# Sheet1.net
KiCad netlist of a schematic drawn in Altium Designer
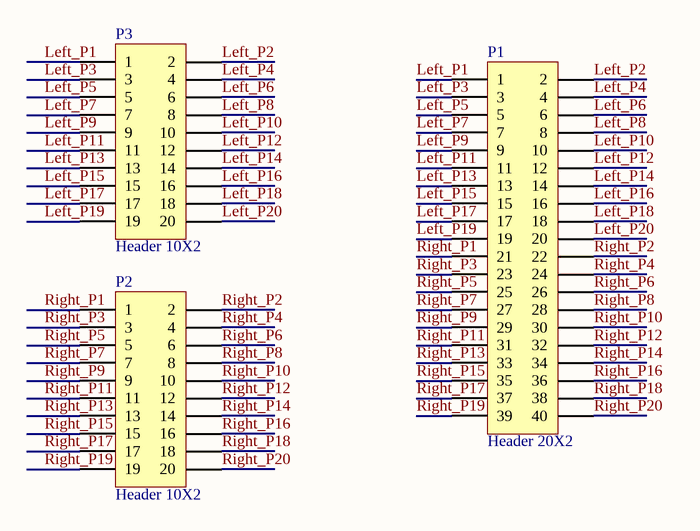
[diagram p0: Sheet1.SchDoc]

(export (version "E")
  (design (tool "Eeschema 10.0.6"))
  (components
    (comp (ref "P1")
      (value "Header 20X2")
      (footprint "BTB0.8con40Pin")
      (description "Header, 20-Pin, Dual row")
      (fields (field (name "PUBLISHER") "Altium Limited"))
      (libsource (lib "Miscellaneous Connectors") (part "Header 20X2"))
    )
    (comp (ref "P2")
      (value "Header 10X2")
      (footprint "HDR2X10")
      (description "Header, 10-Pin, Dual row")
      (fields (field (name "PUBLISHER") "Altium Limited"))
      (libsource (lib "Miscellaneous Connectors") (part "Header 10X2"))
    )
    (comp (ref "P3")
      (value "Header 10X2")
      (footprint "HDR2X10")
      (description "Header, 10-Pin, Dual row")
      (fields (field (name "PUBLISHER") "Altium Limited"))
      (libsource (lib "Miscellaneous Connectors") (part "Header 10X2"))
    )
  )
  (nets
    (net (code "1") (name "/Left_P1") (class "Default")
      (node (ref "P1") (pin "1") (pinfunction "1_1") (pintype "passive"))
      (node (ref "P3") (pin "1") (pinfunction "1_1") (pintype "passive"))
    )
    (net (code "2") (name "/Left_P2") (class "Default")
      (node (ref "P1") (pin "2") (pinfunction "2_2") (pintype "passive"))
      (node (ref "P3") (pin "2") (pinfunction "2_2") (pintype "passive"))
    )
    (net (code "3") (name "/Left_P3") (class "Default")
      (node (ref "P1") (pin "3") (pinfunction "3_3") (pintype "passive"))
      (node (ref "P3") (pin "3") (pinfunction "3_3") (pintype "passive"))
    )
    (net (code "4") (name "/Left_P4") (class "Default")
      (node (ref "P1") (pin "4") (pinfunction "4_4") (pintype "passive"))
      (node (ref "P3") (pin "4") (pinfunction "4_4") (pintype "passive"))
    )
    (net (code "5") (name "/Left_P5") (class "Default")
      (node (ref "P1") (pin "5") (pinfunction "5_5") (pintype "passive"))
      (node (ref "P3") (pin "5") (pinfunction "5_5") (pintype "passive"))
    )
    (net (code "6") (name "/Left_P6") (class "Default")
      (node (ref "P1") (pin "6") (pinfunction "6_6") (pintype "passive"))
      (node (ref "P3") (pin "6") (pinfunction "6_6") (pintype "passive"))
    )
    (net (code "7") (name "/Left_P7") (class "Default")
      (node (ref "P1") (pin "7") (pinfunction "7_7") (pintype "passive"))
      (node (ref "P3") (pin "7") (pinfunction "7_7") (pintype "passive"))
    )
    (net (code "8") (name "/Left_P8") (class "Default")
      (node (ref "P1") (pin "8") (pinfunction "8_8") (pintype "passive"))
      (node (ref "P3") (pin "8") (pinfunction "8_8") (pintype "passive"))
    )
    (net (code "9") (name "/Left_P9") (class "Default")
      (node (ref "P1") (pin "9") (pinfunction "9_9") (pintype "passive"))
      (node (ref "P3") (pin "9") (pinfunction "9_9") (pintype "passive"))
    )
    (net (code "10") (name "/Left_P10") (class "Default")
      (node (ref "P1") (pin "10") (pinfunction "10_10") (pintype "passive"))
      (node (ref "P3") (pin "10") (pinfunction "10_10") (pintype "passive"))
    )
    (net (code "11") (name "/Left_P11") (class "Default")
      (node (ref "P1") (pin "11") (pinfunction "11_11") (pintype "passive"))
      (node (ref "P3") (pin "11") (pinfunction "11_11") (pintype "passive"))
    )
    (net (code "12") (name "/Left_P12") (class "Default")
      (node (ref "P1") (pin "12") (pinfunction "12_12") (pintype "passive"))
      (node (ref "P3") (pin "12") (pinfunction "12_12") (pintype "passive"))
    )
    (net (code "13") (name "/Left_P13") (class "Default")
      (node (ref "P1") (pin "13") (pinfunction "13_13") (pintype "passive"))
      (node (ref "P3") (pin "13") (pinfunction "13_13") (pintype "passive"))
    )
    (net (code "14") (name "/Left_P14") (class "Default")
      (node (ref "P1") (pin "14") (pinfunction "14_14") (pintype "passive"))
      (node (ref "P3") (pin "14") (pinfunction "14_14") (pintype "passive"))
    )
    (net (code "15") (name "/Left_P15") (class "Default")
      (node (ref "P1") (pin "15") (pinfunction "15_15") (pintype "passive"))
      (node (ref "P3") (pin "15") (pinfunction "15_15") (pintype "passive"))
    )
    (net (code "16") (name "/Left_P16") (class "Default")
      (node (ref "P1") (pin "16") (pinfunction "16_16") (pintype "passive"))
      (node (ref "P3") (pin "16") (pinfunction "16_16") (pintype "passive"))
    )
    (net (code "17") (name "/Left_P17") (class "Default")
      (node (ref "P1") (pin "17") (pinfunction "17_17") (pintype "passive"))
      (node (ref "P3") (pin "17") (pinfunction "17_17") (pintype "passive"))
    )
    (net (code "18") (name "/Left_P18") (class "Default")
      (node (ref "P1") (pin "18") (pinfunction "18_18") (pintype "passive"))
      (node (ref "P3") (pin "18") (pinfunction "18_18") (pintype "passive"))
    )
    (net (code "19") (name "/Left_P19") (class "Default")
      (node (ref "P1") (pin "19") (pinfunction "19_19") (pintype "passive"))
      (node (ref "P3") (pin "19") (pinfunction "19_19") (pintype "passive"))
    )
    (net (code "20") (name "/Left_P20") (class "Default")
      (node (ref "P1") (pin "20") (pinfunction "20_20") (pintype "passive"))
      (node (ref "P3") (pin "20") (pinfunction "20_20") (pintype "passive"))
    )
    (net (code "21") (name "/Right_P1") (class "Default")
      (node (ref "P1") (pin "21") (pinfunction "21_21") (pintype "passive"))
      (node (ref "P2") (pin "1") (pinfunction "1_1") (pintype "passive"))
    )
    (net (code "22") (name "/Right_P2") (class "Default")
      (node (ref "P1") (pin "22") (pinfunction "22_22") (pintype "passive"))
      (node (ref "P2") (pin "2") (pinfunction "2_2") (pintype "passive"))
    )
    (net (code "23") (name "/Right_P3") (class "Default")
      (node (ref "P1") (pin "23") (pinfunction "23_23") (pintype "passive"))
      (node (ref "P2") (pin "3") (pinfunction "3_3") (pintype "passive"))
    )
    (net (code "24") (name "/Right_P4") (class "Default")
      (node (ref "P1") (pin "24") (pinfunction "24_24") (pintype "passive"))
      (node (ref "P2") (pin "4") (pinfunction "4_4") (pintype "passive"))
    )
    (net (code "25") (name "/Right_P5") (class "Default")
      (node (ref "P1") (pin "25") (pinfunction "25_25") (pintype "passive"))
      (node (ref "P2") (pin "5") (pinfunction "5_5") (pintype "passive"))
    )
    (net (code "26") (name "/Right_P6") (class "Default")
      (node (ref "P1") (pin "26") (pinfunction "26_26") (pintype "passive"))
      (node (ref "P2") (pin "6") (pinfunction "6_6") (pintype "passive"))
    )
    (net (code "27") (name "/Right_P7") (class "Default")
      (node (ref "P1") (pin "27") (pinfunction "27_27") (pintype "passive"))
      (node (ref "P2") (pin "7") (pinfunction "7_7") (pintype "passive"))
    )
    (net (code "28") (name "/Right_P8") (class "Default")
      (node (ref "P1") (pin "28") (pinfunction "28_28") (pintype "passive"))
      (node (ref "P2") (pin "8") (pinfunction "8_8") (pintype "passive"))
    )
    (net (code "29") (name "/Right_P9") (class "Default")
      (node (ref "P1") (pin "29") (pinfunction "29_29") (pintype "passive"))
      (node (ref "P2") (pin "9") (pinfunction "9_9") (pintype "passive"))
    )
    (net (code "30") (name "/Right_P10") (class "Default")
      (node (ref "P1") (pin "30") (pinfunction "30_30") (pintype "passive"))
      (node (ref "P2") (pin "10") (pinfunction "10_10") (pintype "passive"))
    )
    (net (code "31") (name "/Right_P11") (class "Default")
      (node (ref "P1") (pin "31") (pinfunction "31_31") (pintype "passive"))
      (node (ref "P2") (pin "11") (pinfunction "11_11") (pintype "passive"))
    )
    (net (code "32") (name "/Right_P12") (class "Default")
      (node (ref "P1") (pin "32") (pinfunction "32_32") (pintype "passive"))
      (node (ref "P2") (pin "12") (pinfunction "12_12") (pintype "passive"))
    )
    (net (code "33") (name "/Right_P13") (class "Default")
      (node (ref "P1") (pin "33") (pinfunction "33_33") (pintype "passive"))
      (node (ref "P2") (pin "13") (pinfunction "13_13") (pintype "passive"))
    )
    (net (code "34") (name "/Right_P14") (class "Default")
      (node (ref "P1") (pin "34") (pinfunction "34_34") (pintype "passive"))
      (node (ref "P2") (pin "14") (pinfunction "14_14") (pintype "passive"))
    )
    (net (code "35") (name "/Right_P15") (class "Default")
      (node (ref "P1") (pin "35") (pinfunction "35_35") (pintype "passive"))
      (node (ref "P2") (pin "15") (pinfunction "15_15") (pintype "passive"))
    )
    (net (code "36") (name "/Right_P16") (class "Default")
      (node (ref "P1") (pin "36") (pinfunction "36_36") (pintype "passive"))
      (node (ref "P2") (pin "16") (pinfunction "16_16") (pintype "passive"))
    )
    (net (code "37") (name "/Right_P17") (class "Default")
      (node (ref "P1") (pin "37") (pinfunction "37_37") (pintype "passive"))
      (node (ref "P2") (pin "17") (pinfunction "17_17") (pintype "passive"))
    )
    (net (code "38") (name "/Right_P18") (class "Default")
      (node (ref "P1") (pin "38") (pinfunction "38_38") (pintype "passive"))
      (node (ref "P2") (pin "18") (pinfunction "18_18") (pintype "passive"))
    )
    (net (code "39") (name "/Right_P19") (class "Default")
      (node (ref "P1") (pin "39") (pinfunction "39_39") (pintype "passive"))
      (node (ref "P2") (pin "19") (pinfunction "19_19") (pintype "passive"))
    )
    (net (code "40") (name "/Right_P20") (class "Default")
      (node (ref "P1") (pin "40") (pinfunction "40_40") (pintype "passive"))
      (node (ref "P2") (pin "20") (pinfunction "20_20") (pintype "passive"))
    )
  )
)
